# moire_v1_8.net
KiCad netlist of a schematic drawn in EAGLE
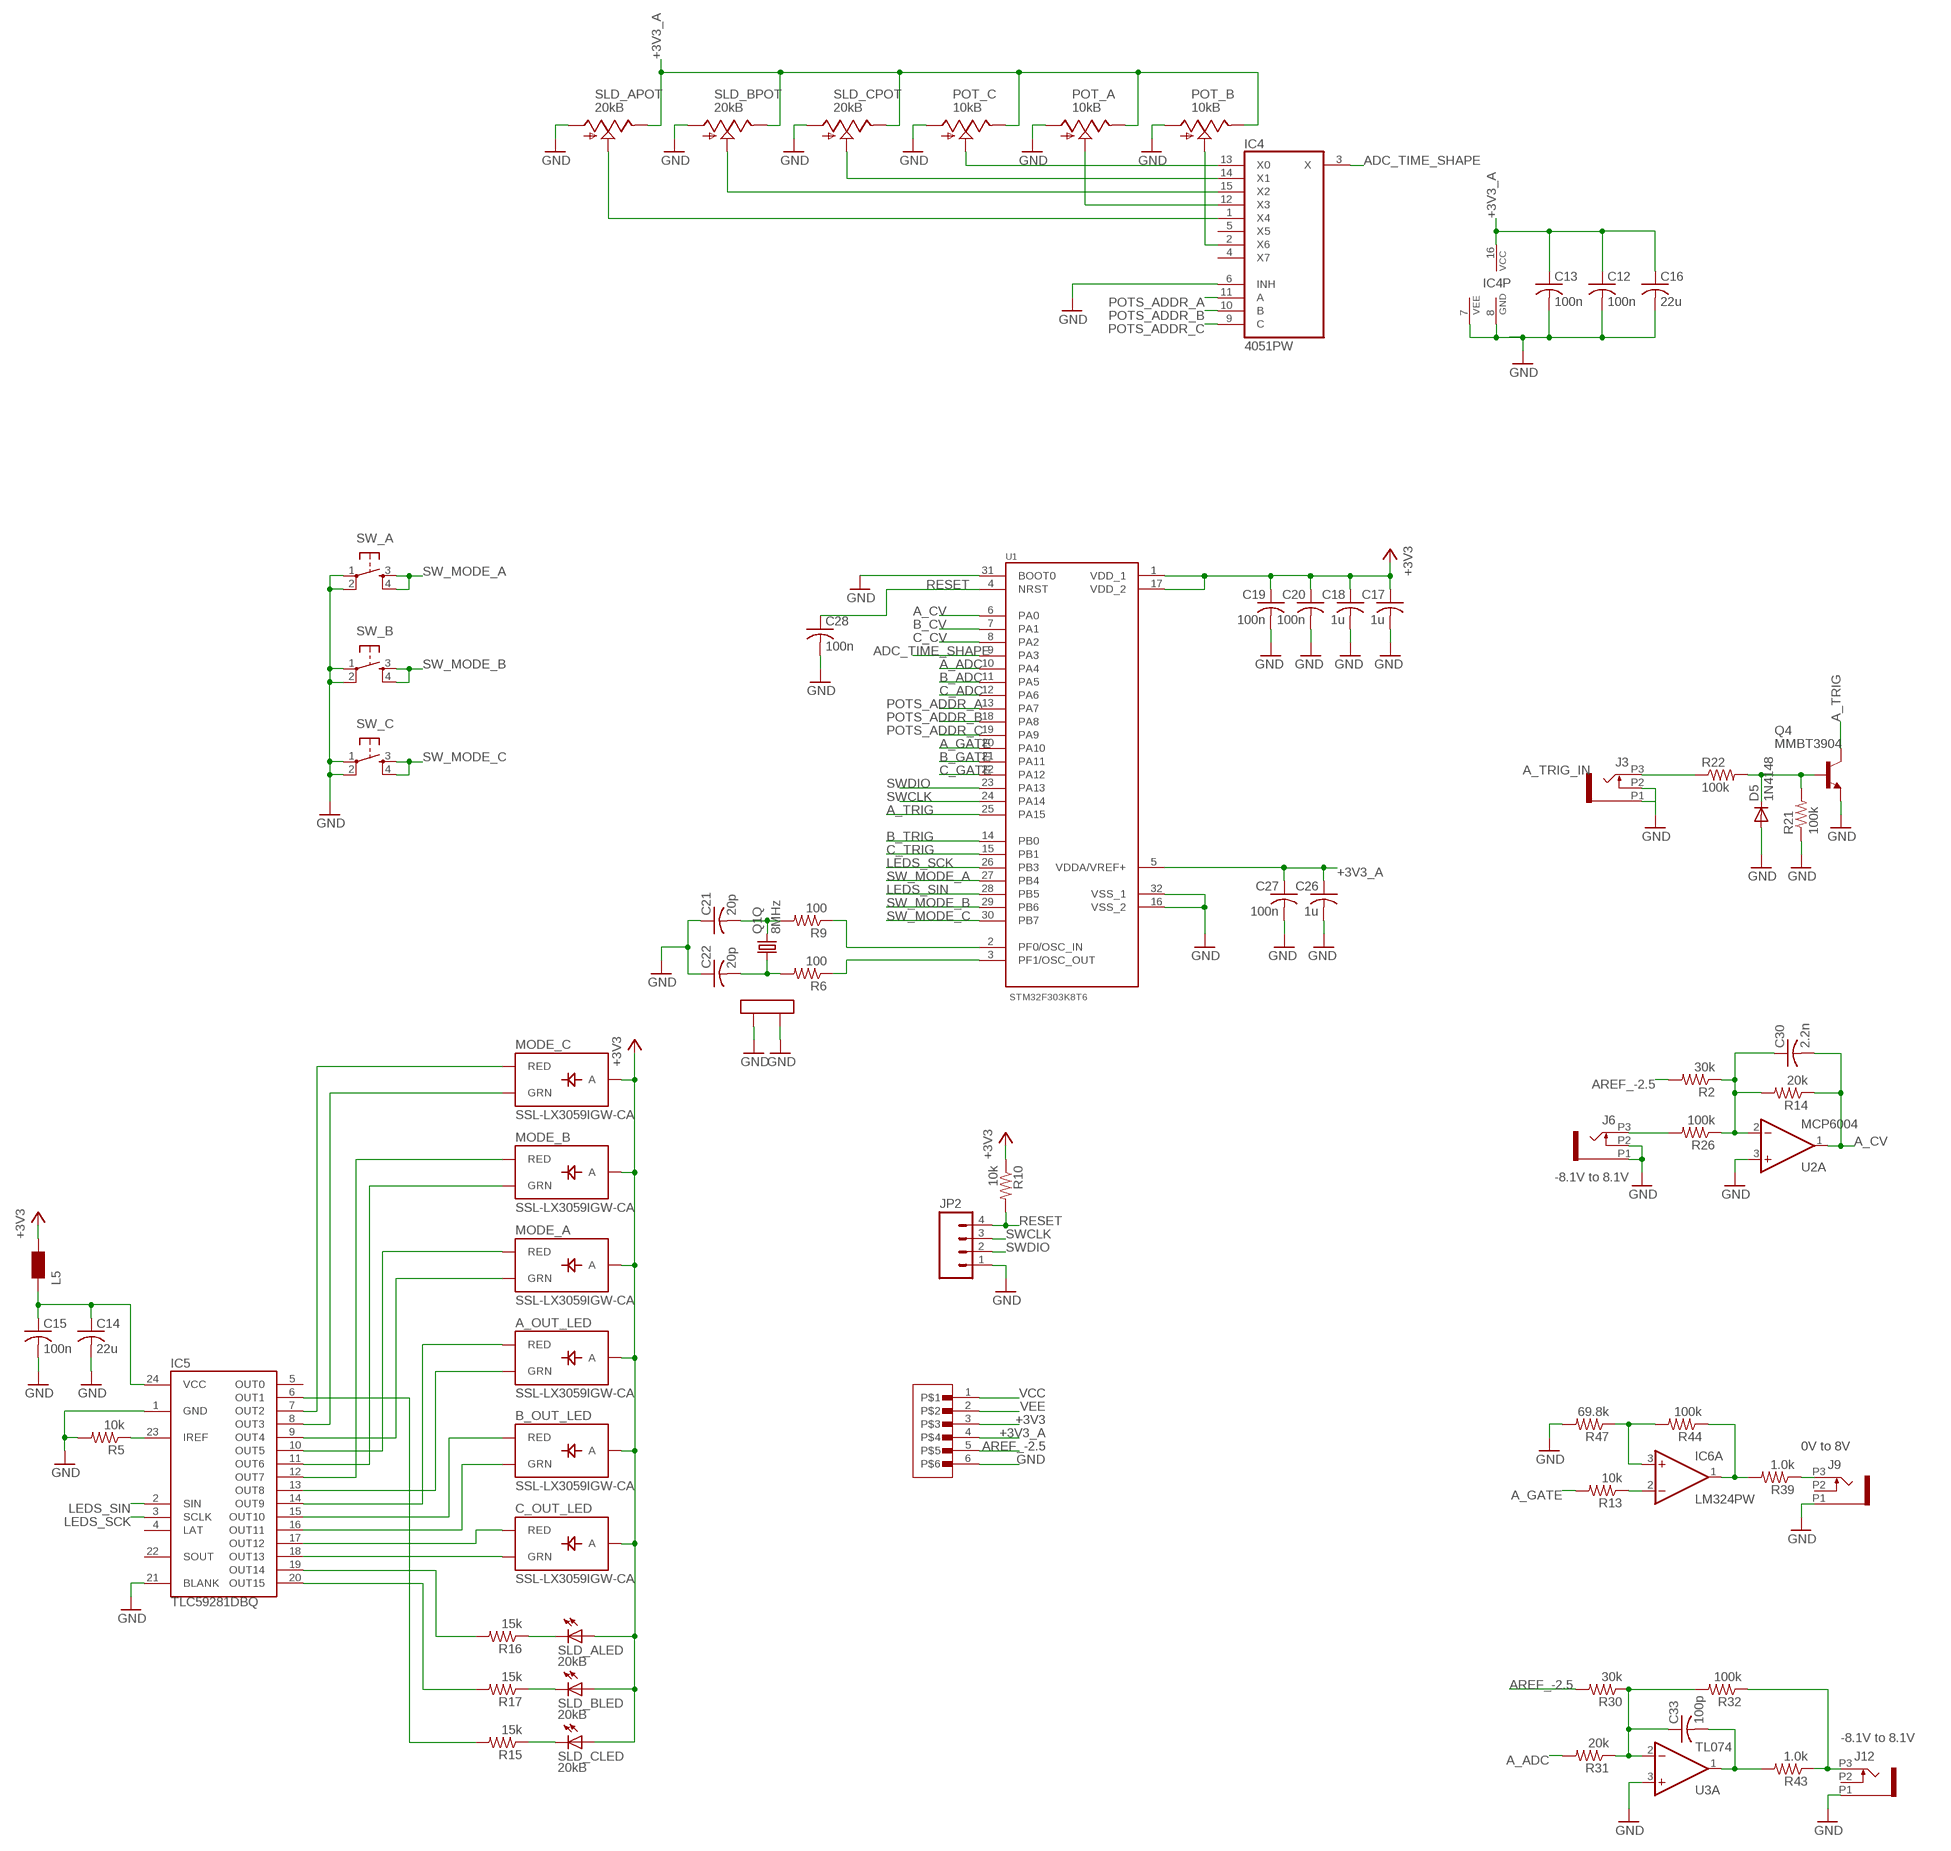
[diagram p0: schematic, sheet 1, part 1 of 2]
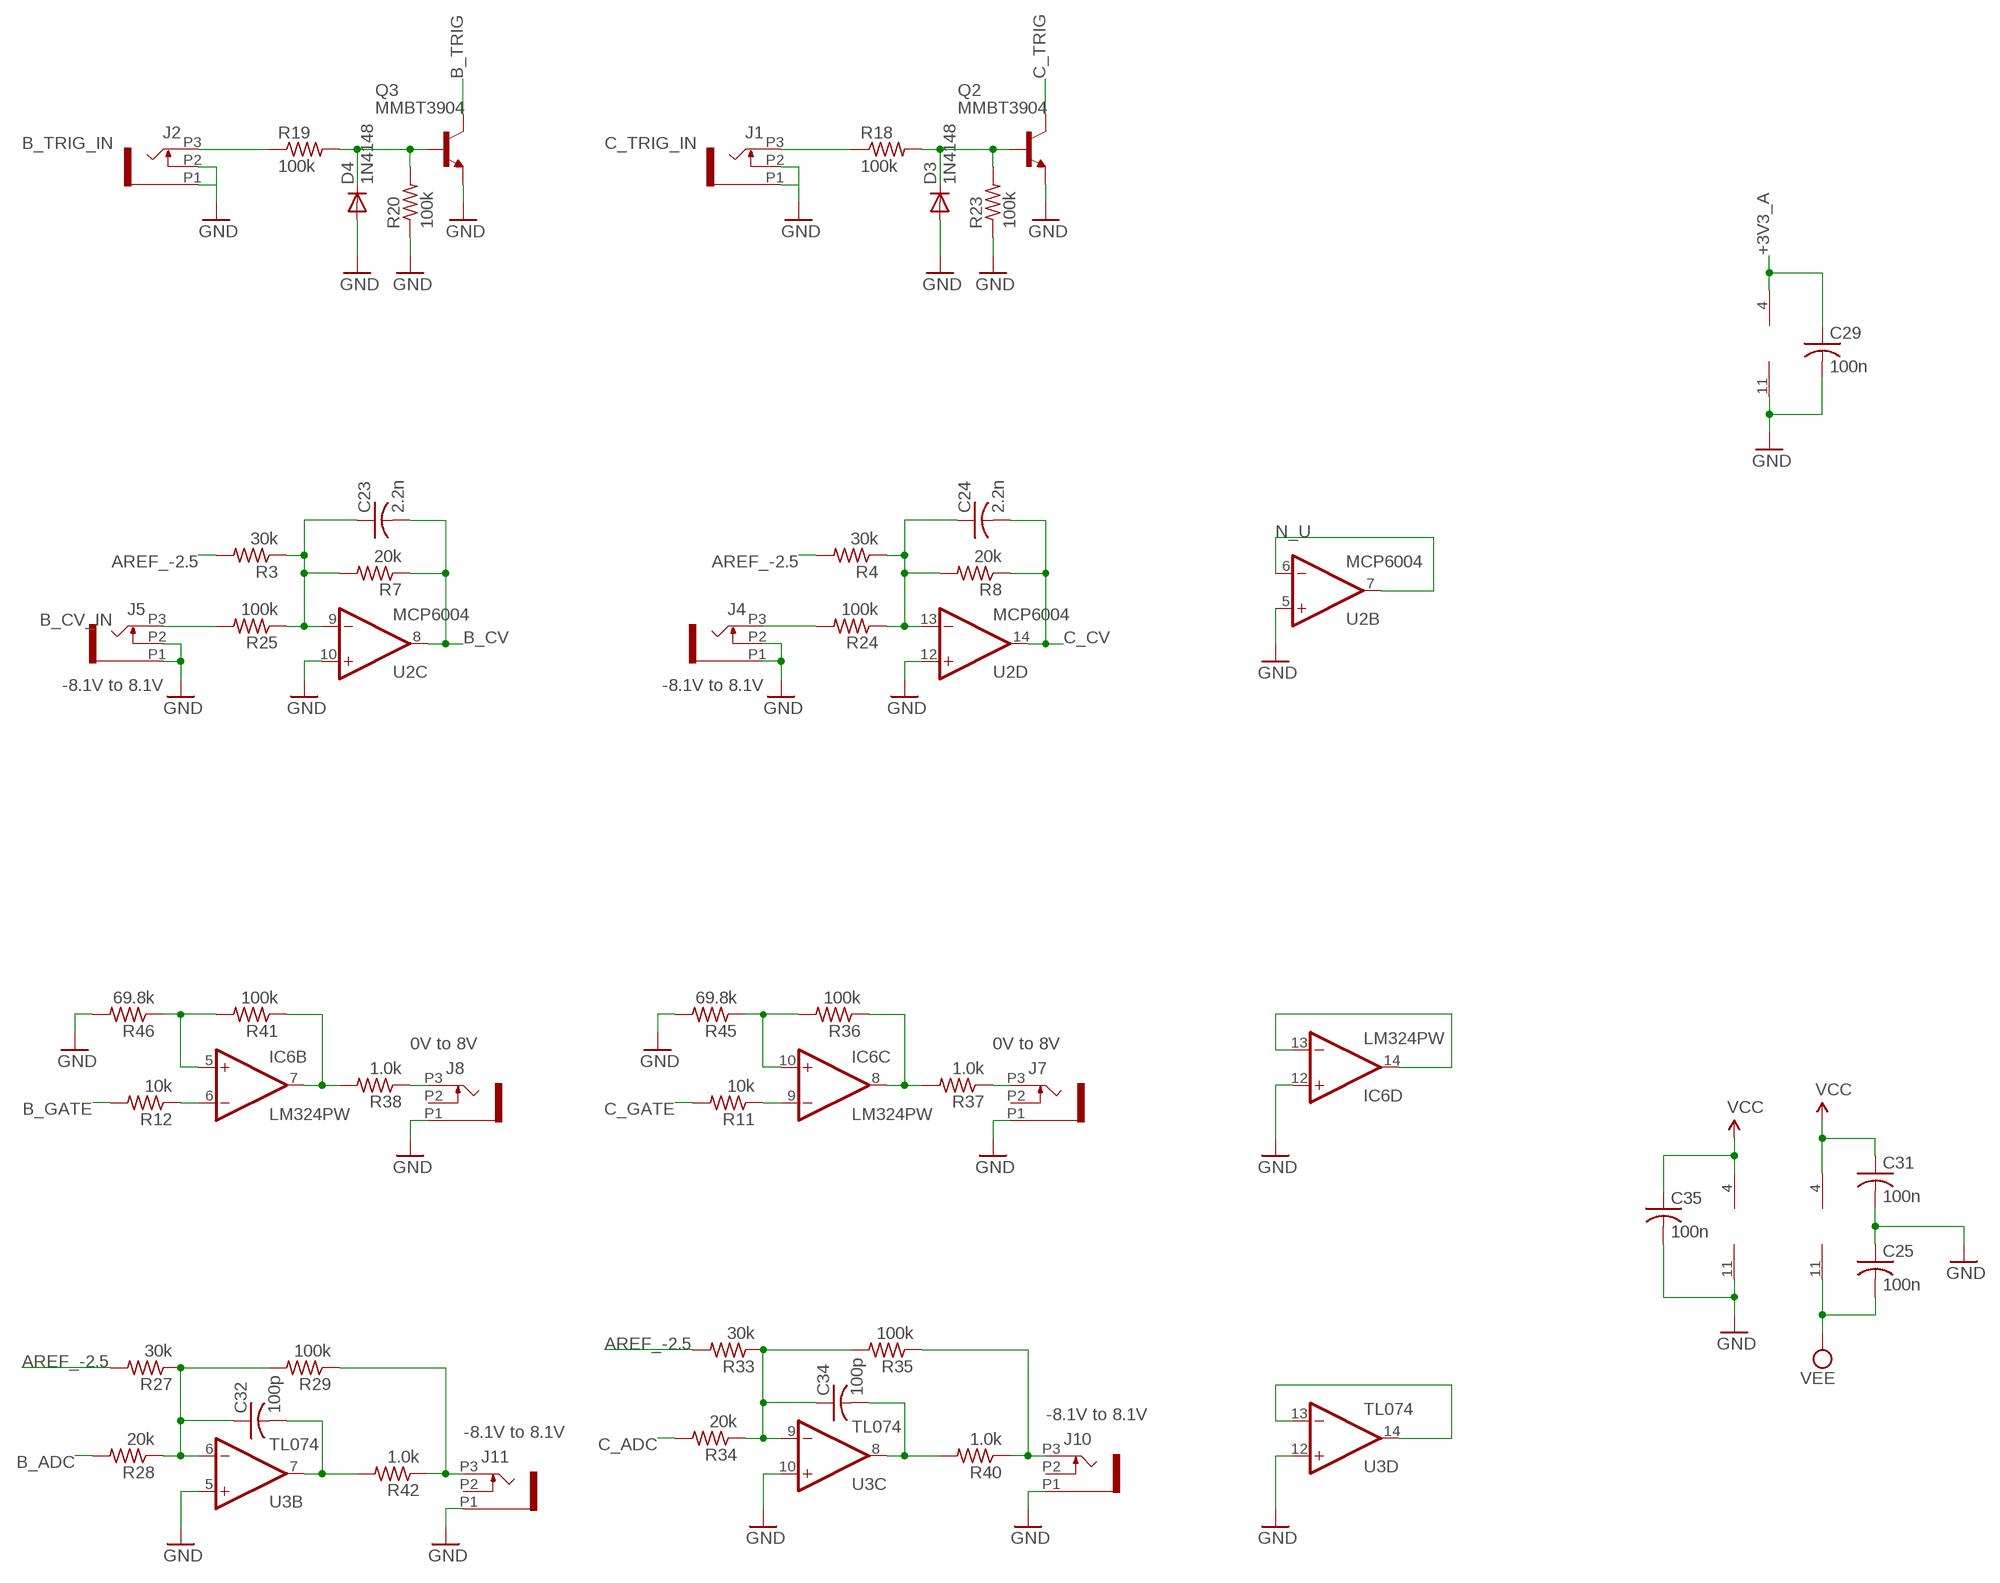
[diagram p1: schematic, sheet 1, part 2 of 2]
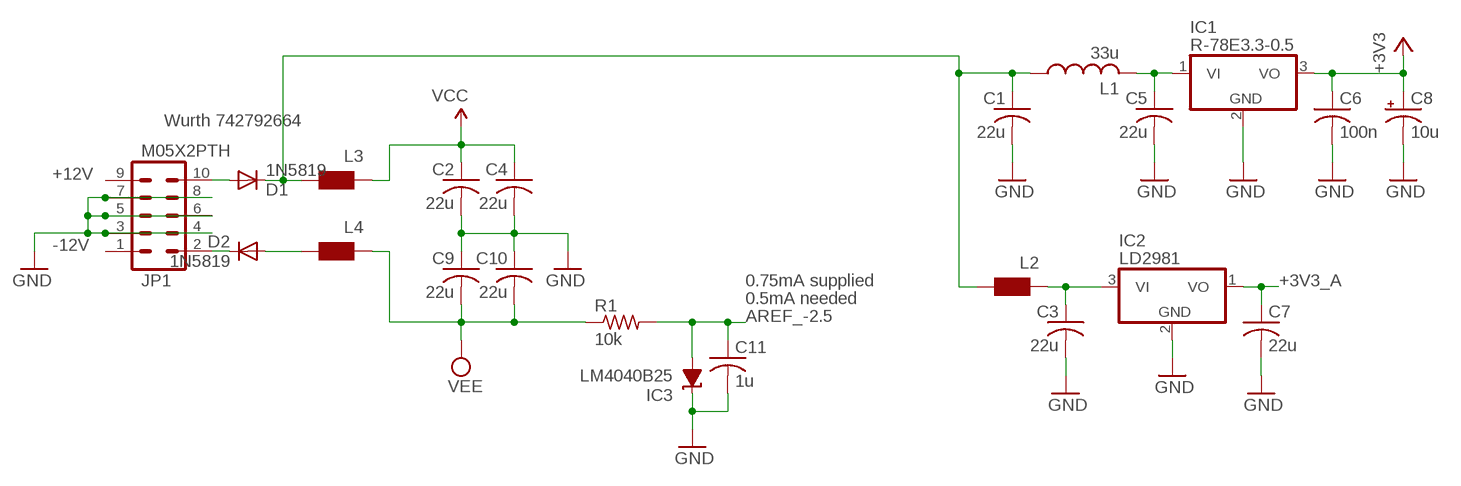
[diagram p2: schematic, sheet 2]

(export (version "E")
  (design (tool "Eeschema 10.0.6"))
  (components
    (comp (ref "C1")
      (value "22u")
      (footprint "eagle-import:RCL_C1206")
      (libsource (lib "eagle-import") (part "RCL_C-USC1206"))
    )
    (comp (ref "C2")
      (value "22u")
      (footprint "eagle-import:RCL_C1206")
      (libsource (lib "eagle-import") (part "RCL_C-USC1206"))
    )
    (comp (ref "C3")
      (value "22u")
      (footprint "eagle-import:RCL_C1206")
      (libsource (lib "eagle-import") (part "RCL_C-USC1206"))
    )
    (comp (ref "C4")
      (value "22u")
      (footprint "eagle-import:RCL_C1206")
      (libsource (lib "eagle-import") (part "RCL_C-USC1206"))
    )
    (comp (ref "C5")
      (value "22u")
      (footprint "eagle-import:RCL_C1206")
      (libsource (lib "eagle-import") (part "RCL_C-USC1206"))
    )
    (comp (ref "C6")
      (value "100n")
      (footprint "eagle-import:RCL_C0603")
      (libsource (lib "eagle-import") (part "RCL_C-USC0603"))
    )
    (comp (ref "C7")
      (value "22u")
      (footprint "eagle-import:RCL_C1206")
      (libsource (lib "eagle-import") (part "RCL_C-USC1206"))
    )
    (comp (ref "C8")
      (value "10u")
      (footprint "eagle-import:RCL_PANASONIC_A")
      (libsource (lib "eagle-import") (part "RCL_CPOL-USA"))
    )
    (comp (ref "C9")
      (value "22u")
      (footprint "eagle-import:RCL_C1206")
      (libsource (lib "eagle-import") (part "RCL_C-USC1206"))
    )
    (comp (ref "C10")
      (value "22u")
      (footprint "eagle-import:RCL_C1206")
      (libsource (lib "eagle-import") (part "RCL_C-USC1206"))
    )
    (comp (ref "C11")
      (value "1u")
      (footprint "eagle-import:RCL_C0603")
      (libsource (lib "eagle-import") (part "RCL_C-USC0603"))
    )
    (comp (ref "D1")
      (value "1N5819")
      (footprint "eagle-import:DIODE_SOD123")
      (libsource (lib "eagle-import") (part "DIODE_DIODE-SOD123"))
    )
    (comp (ref "D2")
      (value "1N5819")
      (footprint "eagle-import:DIODE_SOD123")
      (libsource (lib "eagle-import") (part "DIODE_DIODE-SOD123"))
    )
    (comp (ref "IC1")
      (value "R-78E3.3-0.5")
      (footprint "eagle-import:WE78")
      (libsource (lib "eagle-import") (part "WE173950378"))
    )
    (comp (ref "IC2")
      (value "LD2981")
      (footprint "eagle-import:SOT89")
      (libsource (lib "eagle-import") (part "LD2981ABU"))
    )
    (comp (ref "IC3")
      (value "LM4040B25")
      (footprint "eagle-import:DBZ_R-PDSO-G3")
      (libsource (lib "eagle-import") (part "LM4041DBZB12"))
    )
    (comp (ref "JP1")
      (value "M05X2PTH")
      (footprint "eagle-import:2X5-PTH")
      (libsource (lib "eagle-import") (part "M05X2PTH"))
    )
    (comp (ref "L1")
      (value "33u")
      (footprint "eagle-import:L2012C")
      (libsource (lib "eagle-import") (part "L-USL2012C"))
    )
    (comp (ref "L2")
      (value "WE-CBF_0603")
      (footprint "eagle-import:0603")
      (libsource (lib "eagle-import") (part "WE-CBF_0603"))
    )
    (comp (ref "L3")
      (value "WE-CBF_0603")
      (footprint "eagle-import:0603")
      (libsource (lib "eagle-import") (part "WE-CBF_0603"))
    )
    (comp (ref "L4")
      (value "WE-CBF_0603")
      (footprint "eagle-import:0603")
      (libsource (lib "eagle-import") (part "WE-CBF_0603"))
    )
    (comp (ref "R1")
      (value "10k")
      (footprint "eagle-import:RCL_R0603")
      (libsource (lib "eagle-import") (part "RCL_R-US_R0603"))
    )
    (comp (ref "A_OUT_LED")
      (value "SSL-LX3059IGW-CA")
      (footprint "eagle-import:LED-BICOLOR-THROUGHHOLE-LUMEX")
      (libsource (lib "eagle-import") (part "LED-BICOLOR-THROUGHHOLE-CA"))
    )
    (comp (ref "B_OUT_LED")
      (value "SSL-LX3059IGW-CA")
      (footprint "eagle-import:LED-BICOLOR-THROUGHHOLE-LUMEX")
      (libsource (lib "eagle-import") (part "LED-BICOLOR-THROUGHHOLE-CA"))
    )
    (comp (ref "C12")
      (value "100n")
      (footprint "eagle-import:RCL_C0603")
      (libsource (lib "eagle-import") (part "RCL_C-USC0603"))
    )
    (comp (ref "C13")
      (value "100n")
      (footprint "eagle-import:RCL_C0603")
      (libsource (lib "eagle-import") (part "RCL_C-USC0603"))
    )
    (comp (ref "C14")
      (value "22u")
      (footprint "eagle-import:RCL_C1206")
      (libsource (lib "eagle-import") (part "RCL_C-USC1206"))
    )
    (comp (ref "C15")
      (value "100n")
      (footprint "eagle-import:RCL_C0603")
      (libsource (lib "eagle-import") (part "RCL_C-USC0603"))
    )
    (comp (ref "C16")
      (value "22u")
      (footprint "eagle-import:RCL_C1206")
      (libsource (lib "eagle-import") (part "RCL_C-USC1206"))
    )
    (comp (ref "C17")
      (value "1u")
      (footprint "eagle-import:RCL_C0603")
      (libsource (lib "eagle-import") (part "RCL_C-USC0603"))
    )
    (comp (ref "C18")
      (value "1u")
      (footprint "eagle-import:RCL_C0603")
      (libsource (lib "eagle-import") (part "RCL_C-USC0603"))
    )
    (comp (ref "C19")
      (value "100n")
      (footprint "eagle-import:RCL_C0603")
      (libsource (lib "eagle-import") (part "RCL_C-USC0603"))
    )
    (comp (ref "C20")
      (value "100n")
      (footprint "eagle-import:RCL_C0603")
      (libsource (lib "eagle-import") (part "RCL_C-USC0603"))
    )
    (comp (ref "C21")
      (value "20p")
      (footprint "eagle-import:RCL_C0603")
      (libsource (lib "eagle-import") (part "RCL_C-USC0603"))
    )
    (comp (ref "C22")
      (value "20p")
      (footprint "eagle-import:RCL_C0603")
      (libsource (lib "eagle-import") (part "RCL_C-USC0603"))
    )
    (comp (ref "C23")
      (value "2.2n")
      (footprint "eagle-import:RCL_C0603")
      (libsource (lib "eagle-import") (part "RCL_C-USC0603"))
    )
    (comp (ref "C24")
      (value "2.2n")
      (footprint "eagle-import:RCL_C0603")
      (libsource (lib "eagle-import") (part "RCL_C-USC0603"))
    )
    (comp (ref "C25")
      (value "100n")
      (footprint "eagle-import:RCL_C0603")
      (libsource (lib "eagle-import") (part "RCL_C-USC0603"))
    )
    (comp (ref "C26")
      (value "1u")
      (footprint "eagle-import:RCL_C0603")
      (libsource (lib "eagle-import") (part "RCL_C-USC0603"))
    )
    (comp (ref "C27")
      (value "100n")
      (footprint "eagle-import:RCL_C0603")
      (libsource (lib "eagle-import") (part "RCL_C-USC0603"))
    )
    (comp (ref "C28")
      (value "100n")
      (footprint "eagle-import:RCL_C0603")
      (libsource (lib "eagle-import") (part "RCL_C-USC0603"))
    )
    (comp (ref "C29")
      (value "100n")
      (footprint "eagle-import:RCL_C0603")
      (libsource (lib "eagle-import") (part "RCL_C-USC0603"))
    )
    (comp (ref "C30")
      (value "2.2n")
      (footprint "eagle-import:RCL_C0603")
      (libsource (lib "eagle-import") (part "RCL_C-USC0603"))
    )
    (comp (ref "C31")
      (value "100n")
      (footprint "eagle-import:RCL_C0603")
      (libsource (lib "eagle-import") (part "RCL_C-USC0603"))
    )
    (comp (ref "C32")
      (value "100p")
      (footprint "eagle-import:RCL_C0603")
      (libsource (lib "eagle-import") (part "RCL_C-USC0603"))
    )
    (comp (ref "C33")
      (value "100p")
      (footprint "eagle-import:RCL_C0603")
      (libsource (lib "eagle-import") (part "RCL_C-USC0603"))
    )
    (comp (ref "C34")
      (value "100p")
      (footprint "eagle-import:RCL_C0603")
      (libsource (lib "eagle-import") (part "RCL_C-USC0603"))
    )
    (comp (ref "C35")
      (value "100n")
      (footprint "eagle-import:RCL_C0603")
      (libsource (lib "eagle-import") (part "RCL_C-USC0603"))
    )
    (comp (ref "C_OUT_LED")
      (value "SSL-LX3059IGW-CA")
      (footprint "eagle-import:LED-BICOLOR-THROUGHHOLE-LUMEX")
      (libsource (lib "eagle-import") (part "LED-BICOLOR-THROUGHHOLE-CA"))
    )
    (comp (ref "D3")
      (value "1N4148")
      (footprint "eagle-import:DIODE_SOD523")
      (libsource (lib "eagle-import") (part "DIODE_DIODE-SOD523"))
    )
    (comp (ref "D4")
      (value "1N4148")
      (footprint "eagle-import:DIODE_SOD523")
      (libsource (lib "eagle-import") (part "DIODE_DIODE-SOD523"))
    )
    (comp (ref "D5")
      (value "1N4148")
      (footprint "eagle-import:DIODE_SOD523")
      (libsource (lib "eagle-import") (part "DIODE_DIODE-SOD523"))
    )
    (comp (ref "IC4")
      (value "4051PW")
      (footprint "eagle-import:TSSOP16_065")
      (libsource (lib "eagle-import") (part "4051PW"))
    )
    (comp (ref "IC5")
      (value "TLC59281DBQ")
      (footprint "eagle-import:TSSOP24_0635")
      (libsource (lib "eagle-import") (part "TLC59281DBQ"))
    )
    (comp (ref "IC6")
      (value "LM324PW")
      (footprint "eagle-import:TSSOP14_065")
      (libsource (lib "eagle-import") (part "TL074PW"))
    )
    (comp (ref "J1")
      (value "PJ301_THONKICONN6")
      (footprint "eagle-import:WQP_PJ_301M6")
      (libsource (lib "eagle-import") (part "PJ301_THONKICONN6"))
    )
    (comp (ref "J2")
      (value "PJ301_THONKICONN6")
      (footprint "eagle-import:WQP_PJ_301M6")
      (libsource (lib "eagle-import") (part "PJ301_THONKICONN6"))
    )
    (comp (ref "J3")
      (value "PJ301_THONKICONN6")
      (footprint "eagle-import:WQP_PJ_301M6")
      (libsource (lib "eagle-import") (part "PJ301_THONKICONN6"))
    )
    (comp (ref "J4")
      (value "PJ301_THONKICONN6")
      (footprint "eagle-import:WQP_PJ_301M6")
      (libsource (lib "eagle-import") (part "PJ301_THONKICONN6"))
    )
    (comp (ref "J5")
      (value "PJ301_THONKICONN6")
      (footprint "eagle-import:WQP_PJ_301M6")
      (libsource (lib "eagle-import") (part "PJ301_THONKICONN6"))
    )
    (comp (ref "J6")
      (value "PJ301_THONKICONN6")
      (footprint "eagle-import:WQP_PJ_301M6")
      (libsource (lib "eagle-import") (part "PJ301_THONKICONN6"))
    )
    (comp (ref "J7")
      (value "PJ301_THONKICONN6")
      (footprint "eagle-import:WQP_PJ_301M6")
      (libsource (lib "eagle-import") (part "PJ301_THONKICONN6"))
    )
    (comp (ref "J8")
      (value "PJ301_THONKICONN6")
      (footprint "eagle-import:WQP_PJ_301M6")
      (libsource (lib "eagle-import") (part "PJ301_THONKICONN6"))
    )
    (comp (ref "J9")
      (value "PJ301_THONKICONN6")
      (footprint "eagle-import:WQP_PJ_301M6")
      (libsource (lib "eagle-import") (part "PJ301_THONKICONN6"))
    )
    (comp (ref "J10")
      (value "PJ301_THONKICONN6")
      (footprint "eagle-import:WQP_PJ_301M6")
      (libsource (lib "eagle-import") (part "PJ301_THONKICONN6"))
    )
    (comp (ref "J11")
      (value "PJ301_THONKICONN6")
      (footprint "eagle-import:WQP_PJ_301M6")
      (libsource (lib "eagle-import") (part "PJ301_THONKICONN6"))
    )
    (comp (ref "J12")
      (value "PJ301_THONKICONN6")
      (footprint "eagle-import:WQP_PJ_301M6")
      (libsource (lib "eagle-import") (part "PJ301_THONKICONN6"))
    )
    (comp (ref "JP2")
      (value "M04PTH")
      (footprint "eagle-import:1X04")
      (libsource (lib "eagle-import") (part "M04PTH"))
    )
    (comp (ref "L5")
      (value "WE-CBF_0603")
      (footprint "eagle-import:0603")
      (libsource (lib "eagle-import") (part "WE-CBF_0603"))
    )
    (comp (ref "MODE_A")
      (value "SSL-LX3059IGW-CA")
      (footprint "eagle-import:LED-BICOLOR-THROUGHHOLE-LUMEX")
      (libsource (lib "eagle-import") (part "LED-BICOLOR-THROUGHHOLE-CA"))
    )
    (comp (ref "MODE_B")
      (value "SSL-LX3059IGW-CA")
      (footprint "eagle-import:LED-BICOLOR-THROUGHHOLE-LUMEX")
      (libsource (lib "eagle-import") (part "LED-BICOLOR-THROUGHHOLE-CA"))
    )
    (comp (ref "MODE_C")
      (value "SSL-LX3059IGW-CA")
      (footprint "eagle-import:LED-BICOLOR-THROUGHHOLE-LUMEX")
      (libsource (lib "eagle-import") (part "LED-BICOLOR-THROUGHHOLE-CA"))
    )
    (comp (ref "POT_A")
      (value "10kB")
      (footprint "eagle-import:ALPS_POT_VERTICAL")
      (libsource (lib "eagle-import") (part "POT_USVERTICAL"))
    )
    (comp (ref "POT_B")
      (value "10kB")
      (footprint "eagle-import:ALPS_POT_VERTICAL")
      (libsource (lib "eagle-import") (part "POT_USVERTICAL"))
    )
    (comp (ref "POT_C")
      (value "10kB")
      (footprint "eagle-import:ALPS_POT_VERTICAL")
      (libsource (lib "eagle-import") (part "POT_USVERTICAL"))
    )
    (comp (ref "Q1")
      (value "8MHz")
      (footprint "eagle-import:CTS406")
      (libsource (lib "eagle-import") (part "CRYSTAL"))
    )
    (comp (ref "Q2")
      (value "MMBT3904")
      (footprint "eagle-import:SOT23-BEC")
      (libsource (lib "eagle-import") (part "-NPN-SOT23-BECMMBT3904LT1"))
    )
    (comp (ref "Q3")
      (value "MMBT3904")
      (footprint "eagle-import:SOT23-BEC")
      (libsource (lib "eagle-import") (part "-NPN-SOT23-BECMMBT3904LT1"))
    )
    (comp (ref "Q4")
      (value "MMBT3904")
      (footprint "eagle-import:SOT23-BEC")
      (libsource (lib "eagle-import") (part "-NPN-SOT23-BECMMBT3904LT1"))
    )
    (comp (ref "R2")
      (value "30k")
      (footprint "eagle-import:RCL_R0603")
      (libsource (lib "eagle-import") (part "RCL_R-US_R0603"))
    )
    (comp (ref "R3")
      (value "30k")
      (footprint "eagle-import:RCL_R0603")
      (libsource (lib "eagle-import") (part "RCL_R-US_R0603"))
    )
    (comp (ref "R4")
      (value "30k")
      (footprint "eagle-import:RCL_R0603")
      (libsource (lib "eagle-import") (part "RCL_R-US_R0603"))
    )
    (comp (ref "R5")
      (value "10k")
      (footprint "eagle-import:RCL_R0603")
      (libsource (lib "eagle-import") (part "RCL_R-US_R0603"))
    )
    (comp (ref "R6")
      (value "100")
      (footprint "eagle-import:RCL_R0603")
      (libsource (lib "eagle-import") (part "RCL_R-US_R0603"))
    )
    (comp (ref "R7")
      (value "20k")
      (footprint "eagle-import:RCL_R0603")
      (libsource (lib "eagle-import") (part "RCL_R-US_R0603"))
    )
    (comp (ref "R8")
      (value "20k")
      (footprint "eagle-import:RCL_R0603")
      (libsource (lib "eagle-import") (part "RCL_R-US_R0603"))
    )
    (comp (ref "R9")
      (value "100")
      (footprint "eagle-import:RCL_R0603")
      (libsource (lib "eagle-import") (part "RCL_R-US_R0603"))
    )
    (comp (ref "R10")
      (value "10k")
      (footprint "eagle-import:RCL_R0603")
      (libsource (lib "eagle-import") (part "RCL_R-US_R0603"))
    )
    (comp (ref "R11")
      (value "10k")
      (footprint "eagle-import:RCL_R0603")
      (libsource (lib "eagle-import") (part "RCL_R-US_R0603"))
    )
    (comp (ref "R12")
      (value "10k")
      (footprint "eagle-import:RCL_R0603")
      (libsource (lib "eagle-import") (part "RCL_R-US_R0603"))
    )
    (comp (ref "R13")
      (value "10k")
      (footprint "eagle-import:RCL_R0603")
      (libsource (lib "eagle-import") (part "RCL_R-US_R0603"))
    )
    (comp (ref "R14")
      (value "20k")
      (footprint "eagle-import:RCL_R0603")
      (libsource (lib "eagle-import") (part "RCL_R-US_R0603"))
    )
    (comp (ref "R15")
      (value "15k")
      (footprint "eagle-import:RCL_R0603")
      (libsource (lib "eagle-import") (part "RCL_R-US_R0603"))
    )
    (comp (ref "R16")
      (value "15k")
      (footprint "eagle-import:RCL_R0603")
      (libsource (lib "eagle-import") (part "RCL_R-US_R0603"))
    )
    (comp (ref "R17")
      (value "15k")
      (footprint "eagle-import:RCL_R0603")
      (libsource (lib "eagle-import") (part "RCL_R-US_R0603"))
    )
    (comp (ref "R18")
      (value "100k")
      (footprint "eagle-import:RCL_R0603")
      (libsource (lib "eagle-import") (part "RCL_R-US_R0603"))
    )
    (comp (ref "R19")
      (value "100k")
      (footprint "eagle-import:RCL_R0603")
      (libsource (lib "eagle-import") (part "RCL_R-US_R0603"))
    )
    (comp (ref "R20")
      (value "100k")
      (footprint "eagle-import:RCL_R0603")
      (libsource (lib "eagle-import") (part "RCL_R-US_R0603"))
    )
    (comp (ref "R21")
      (value "100k")
      (footprint "eagle-import:RCL_R0603")
      (libsource (lib "eagle-import") (part "RCL_R-US_R0603"))
    )
    (comp (ref "R22")
      (value "100k")
      (footprint "eagle-import:RCL_R0603")
      (libsource (lib "eagle-import") (part "RCL_R-US_R0603"))
    )
    (comp (ref "R23")
      (value "100k")
      (footprint "eagle-import:RCL_R0603")
      (libsource (lib "eagle-import") (part "RCL_R-US_R0603"))
    )
    (comp (ref "R24")
      (value "100k")
      (footprint "eagle-import:RCL_R0603")
      (libsource (lib "eagle-import") (part "RCL_R-US_R0603"))
    )
    (comp (ref "R25")
      (value "100k")
      (footprint "eagle-import:RCL_R0603")
      (libsource (lib "eagle-import") (part "RCL_R-US_R0603"))
    )
    (comp (ref "R26")
      (value "100k")
      (footprint "eagle-import:RCL_R0603")
      (libsource (lib "eagle-import") (part "RCL_R-US_R0603"))
    )
    (comp (ref "R27")
      (value "30k")
      (footprint "eagle-import:RCL_R0603")
      (libsource (lib "eagle-import") (part "RCL_R-US_R0603"))
    )
    (comp (ref "R28")
      (value "20k")
      (footprint "eagle-import:RCL_R0603")
      (libsource (lib "eagle-import") (part "RCL_R-US_R0603"))
    )
    (comp (ref "R29")
      (value "100k")
      (footprint "eagle-import:RCL_R0603")
      (libsource (lib "eagle-import") (part "RCL_R-US_R0603"))
    )
    (comp (ref "R30")
      (value "30k")
      (footprint "eagle-import:RCL_R0603")
      (libsource (lib "eagle-import") (part "RCL_R-US_R0603"))
    )
    (comp (ref "R31")
      (value "20k")
      (footprint "eagle-import:RCL_R0603")
      (libsource (lib "eagle-import") (part "RCL_R-US_R0603"))
    )
    (comp (ref "R32")
      (value "100k")
      (footprint "eagle-import:RCL_R0603")
      (libsource (lib "eagle-import") (part "RCL_R-US_R0603"))
    )
    (comp (ref "R33")
      (value "30k")
      (footprint "eagle-import:RCL_R0603")
      (libsource (lib "eagle-import") (part "RCL_R-US_R0603"))
    )
    (comp (ref "R34")
      (value "20k")
      (footprint "eagle-import:RCL_R0603")
      (libsource (lib "eagle-import") (part "RCL_R-US_R0603"))
    )
    (comp (ref "R35")
      (value "100k")
      (footprint "eagle-import:RCL_R0603")
      (libsource (lib "eagle-import") (part "RCL_R-US_R0603"))
    )
    (comp (ref "R36")
      (value "100k")
      (footprint "eagle-import:RCL_R0603")
      (libsource (lib "eagle-import") (part "RCL_R-US_R0603"))
    )
    (comp (ref "R37")
      (value "1.0k")
      (footprint "eagle-import:RCL_R0603")
      (libsource (lib "eagle-import") (part "RCL_R-US_R0603"))
    )
    (comp (ref "R38")
      (value "1.0k")
      (footprint "eagle-import:RCL_R0603")
      (libsource (lib "eagle-import") (part "RCL_R-US_R0603"))
    )
    (comp (ref "R39")
      (value "1.0k")
      (footprint "eagle-import:RCL_R0603")
      (libsource (lib "eagle-import") (part "RCL_R-US_R0603"))
    )
    (comp (ref "R40")
      (value "1.0k")
      (footprint "eagle-import:RCL_R0603")
      (libsource (lib "eagle-import") (part "RCL_R-US_R0603"))
    )
    (comp (ref "R41")
      (value "100k")
      (footprint "eagle-import:RCL_R0603")
      (libsource (lib "eagle-import") (part "RCL_R-US_R0603"))
    )
    (comp (ref "R42")
      (value "1.0k")
      (footprint "eagle-import:RCL_R0603")
      (libsource (lib "eagle-import") (part "RCL_R-US_R0603"))
    )
    (comp (ref "R43")
      (value "1.0k")
      (footprint "eagle-import:RCL_R0603")
      (libsource (lib "eagle-import") (part "RCL_R-US_R0603"))
    )
    (comp (ref "R44")
      (value "100k")
      (footprint "eagle-import:RCL_R0603")
      (libsource (lib "eagle-import") (part "RCL_R-US_R0603"))
    )
    (comp (ref "R45")
      (value "69.8k")
      (footprint "eagle-import:RCL_R0603")
      (libsource (lib "eagle-import") (part "RCL_R-US_R0603"))
    )
    (comp (ref "R46")
      (value "69.8k")
      (footprint "eagle-import:RCL_R0603")
      (libsource (lib "eagle-import") (part "RCL_R-US_R0603"))
    )
    (comp (ref "R47")
      (value "69.8k")
      (footprint "eagle-import:RCL_R0603")
      (libsource (lib "eagle-import") (part "RCL_R-US_R0603"))
    )
    (comp (ref "SLD_A")
      (value "20kB")
      (footprint "eagle-import:BOURNS_SLIDER")
      (libsource (lib "eagle-import") (part "BOURNS_SLIDER"))
    )
    (comp (ref "SLD_B")
      (value "20kB")
      (footprint "eagle-import:BOURNS_SLIDER")
      (libsource (lib "eagle-import") (part "BOURNS_SLIDER"))
    )
    (comp (ref "SLD_C")
      (value "20kB")
      (footprint "eagle-import:BOURNS_SLIDER")
      (libsource (lib "eagle-import") (part "BOURNS_SLIDER"))
    )
    (comp (ref "SW_A")
      (value "TAC_SWITCHPTH")
      (footprint "eagle-import:TACTILE-PTH")
      (libsource (lib "eagle-import") (part "TAC_SWITCHPTH"))
    )
    (comp (ref "SW_B")
      (value "TAC_SWITCHPTH")
      (footprint "eagle-import:TACTILE-PTH")
      (libsource (lib "eagle-import") (part "TAC_SWITCHPTH"))
    )
    (comp (ref "SW_C")
      (value "TAC_SWITCHPTH")
      (footprint "eagle-import:TACTILE-PTH")
      (libsource (lib "eagle-import") (part "TAC_SWITCHPTH"))
    )
    (comp (ref "U$1")
      (value "1X6-SMD-TESTPAD")
      (footprint "eagle-import:6X1-SMD-TESTPAD")
      (libsource (lib "eagle-import") (part "1X6-SMD-TESTPAD"))
    )
    (comp (ref "U1")
      (value "STM32F303K8T6")
      (footprint "eagle-import:QFP80P900X900X160-32N")
      (fields (field (name "MF") "STMicroelectronics"))
      (libsource (lib "eagle-import") (part "STM32F303K8T6"))
    )
    (comp (ref "U2")
      (value "MCP6004")
      (footprint "eagle-import:SO14")
      (libsource (lib "eagle-import") (part "MCP6004_SMD"))
    )
    (comp (ref "U3")
      (value "TL074")
      (footprint "eagle-import:SO14")
      (libsource (lib "eagle-import") (part "TL074_SMD"))
    )
  )
  (nets
    (net (code "1") (name "+3V3") (class "Default")
      (node (ref "A_OUT_LED") (pin "A") (pinfunction "A_A") (pintype "bidirectional"))
      (node (ref "B_OUT_LED") (pin "A") (pinfunction "A_A") (pintype "bidirectional"))
      (node (ref "C17") (pin "1") (pinfunction "1_1") (pintype "passive"))
      (node (ref "C18") (pin "1") (pinfunction "1_1") (pintype "passive"))
      (node (ref "C19") (pin "1") (pinfunction "1_1") (pintype "passive"))
      (node (ref "C20") (pin "1") (pinfunction "1_1") (pintype "passive"))
      (node (ref "C6") (pin "1") (pinfunction "1_1") (pintype "passive"))
      (node (ref "C8") (pin "+") (pinfunction "+_+") (pintype "passive"))
      (node (ref "C_OUT_LED") (pin "A") (pinfunction "A_A") (pintype "bidirectional"))
      (node (ref "IC1") (pin "3") (pinfunction "VO_3") (pintype "passive"))
      (node (ref "L5") (pin "2") (pinfunction "2_2") (pintype "passive"))
      (node (ref "MODE_A") (pin "A") (pinfunction "A_A") (pintype "bidirectional"))
      (node (ref "MODE_B") (pin "A") (pinfunction "A_A") (pintype "bidirectional"))
      (node (ref "MODE_C") (pin "A") (pinfunction "A_A") (pintype "bidirectional"))
      (node (ref "R10") (pin "1") (pinfunction "1_1") (pintype "passive"))
      (node (ref "SLD_A") (pin "B") (pinfunction "A_B") (pintype "passive"))
      (node (ref "SLD_B") (pin "B") (pinfunction "A_B") (pintype "passive"))
      (node (ref "SLD_C") (pin "B") (pinfunction "A_B") (pintype "passive"))
      (node (ref "U$1") (pin "3") (pinfunction "P$3_3") (pintype "bidirectional"))
      (node (ref "U1") (pin "1") (pinfunction "VDD_1_1") (pintype "power_in"))
      (node (ref "U1") (pin "17") (pinfunction "VDD_2_17") (pintype "power_in"))
    )
    (net (code "2") (name "+3V3_A") (class "Default")
      (node (ref "C12") (pin "1") (pinfunction "1_1") (pintype "passive"))
      (node (ref "C13") (pin "1") (pinfunction "1_1") (pintype "passive"))
      (node (ref "C16") (pin "1") (pinfunction "1_1") (pintype "passive"))
      (node (ref "C26") (pin "1") (pinfunction "1_1") (pintype "passive"))
      (node (ref "C27") (pin "1") (pinfunction "1_1") (pintype "passive"))
      (node (ref "C29") (pin "1") (pinfunction "1_1") (pintype "passive"))
      (node (ref "C7") (pin "1") (pinfunction "1_1") (pintype "passive"))
      (node (ref "IC2") (pin "1") (pinfunction "VO_1") (pintype "passive"))
      (node (ref "IC4") (pin "16") (pinfunction "VCC_16") (pintype "power_in"))
      (node (ref "POT_A") (pin "P$1") (pinfunction "E_P$1") (pintype "passive"))
      (node (ref "POT_B") (pin "P$1") (pinfunction "E_P$1") (pintype "passive"))
      (node (ref "POT_C") (pin "P$1") (pinfunction "E_P$1") (pintype "passive"))
      (node (ref "SLD_A") (pin "3") (pinfunction "E_3") (pintype "passive"))
      (node (ref "SLD_B") (pin "3") (pinfunction "E_3") (pintype "passive"))
      (node (ref "SLD_C") (pin "3") (pinfunction "E_3") (pintype "passive"))
      (node (ref "U$1") (pin "4") (pinfunction "P$4_4") (pintype "bidirectional"))
      (node (ref "U1") (pin "5") (pinfunction "VDDA/VREF+_5") (pintype "power_in"))
      (node (ref "U2") (pin "4") (pinfunction "V+_4") (pintype "power_in"))
    )
    (net (code "3") (name "+12V") (class "Default")
      (node (ref "D1") (pin "A") (pinfunction "A_A") (pintype "passive"))
      (node (ref "JP1") (pin "10") (pinfunction "10_10") (pintype "passive"))
      (node (ref "JP1") (pin "9") (pinfunction "9_9") (pintype "passive"))
    )
    (net (code "4") (name "-12V") (class "Default")
      (node (ref "D2") (pin "C") (pinfunction "C_C") (pintype "passive"))
      (node (ref "JP1") (pin "1") (pinfunction "1_1") (pintype "passive"))
      (node (ref "JP1") (pin "2") (pinfunction "2_2") (pintype "passive"))
    )
    (net (code "5") (name "ADC_TIME_SHAPE") (class "Default")
      (node (ref "IC4") (pin "3") (pinfunction "X_3") (pintype "bidirectional"))
      (node (ref "U1") (pin "9") (pinfunction "PA3_9") (pintype "bidirectional"))
    )
    (net (code "6") (name "AREF_-2.5") (class "Default")
      (node (ref "C11") (pin "1") (pinfunction "1_1") (pintype "passive"))
      (node (ref "IC3") (pin "2") (pinfunction "A_2") (pintype "passive"))
      (node (ref "R1") (pin "2") (pinfunction "2_2") (pintype "passive"))
      (node (ref "R2") (pin "2") (pinfunction "2_2") (pintype "passive"))
      (node (ref "R27") (pin "2") (pinfunction "2_2") (pintype "passive"))
      (node (ref "R3") (pin "2") (pinfunction "2_2") (pintype "passive"))
      (node (ref "R30") (pin "2") (pinfunction "2_2") (pintype "passive"))
      (node (ref "R33") (pin "2") (pinfunction "2_2") (pintype "passive"))
      (node (ref "R4") (pin "2") (pinfunction "2_2") (pintype "passive"))
      (node (ref "U$1") (pin "5") (pinfunction "P$5_5") (pintype "bidirectional"))
    )
    (net (code "7") (name "A_ADC") (class "Default")
      (node (ref "R31") (pin "2") (pinfunction "2_2") (pintype "passive"))
      (node (ref "U1") (pin "10") (pinfunction "PA4_10") (pintype "bidirectional"))
    )
    (net (code "8") (name "A_CV") (class "Default")
      (node (ref "C30") (pin "2") (pinfunction "2_2") (pintype "passive"))
      (node (ref "R14") (pin "1") (pinfunction "1_1") (pintype "passive"))
      (node (ref "U1") (pin "6") (pinfunction "PA0_6") (pintype "bidirectional"))
      (node (ref "U2") (pin "1") (pinfunction "OUT_1") (pintype "output"))
    )
    (net (code "9") (name "A_GATE") (class "Default")
      (node (ref "R13") (pin "2") (pinfunction "2_2") (pintype "passive"))
      (node (ref "U1") (pin "20") (pinfunction "PA10_20") (pintype "bidirectional"))
    )
    (net (code "10") (name "A_TRIG") (class "Default")
      (node (ref "Q4") (pin "C") (pinfunction "C_C") (pintype "passive"))
      (node (ref "U1") (pin "25") (pinfunction "PA15_25") (pintype "bidirectional"))
    )
    (net (code "11") (name "A_TRIG_IN") (class "Default")
      (node (ref "J3") (pin "P3") (pinfunction "3_P3") (pintype "passive"))
      (node (ref "R22") (pin "1") (pinfunction "1_1") (pintype "passive"))
    )
    (net (code "12") (name "B_ADC") (class "Default")
      (node (ref "R28") (pin "2") (pinfunction "2_2") (pintype "passive"))
      (node (ref "U1") (pin "11") (pinfunction "PA5_11") (pintype "bidirectional"))
    )
    (net (code "13") (name "B_CV") (class "Default")
      (node (ref "C23") (pin "2") (pinfunction "2_2") (pintype "passive"))
      (node (ref "R7") (pin "1") (pinfunction "1_1") (pintype "passive"))
      (node (ref "U1") (pin "7") (pinfunction "PA1_7") (pintype "bidirectional"))
      (node (ref "U2") (pin "8") (pinfunction "OUT_8") (pintype "output"))
    )
    (net (code "14") (name "B_CV_IN") (class "Default")
      (node (ref "J5") (pin "P3") (pinfunction "3_P3") (pintype "passive"))
      (node (ref "R25") (pin "2") (pinfunction "2_2") (pintype "passive"))
    )
    (net (code "15") (name "B_GATE") (class "Default")
      (node (ref "R12") (pin "2") (pinfunction "2_2") (pintype "passive"))
      (node (ref "U1") (pin "21") (pinfunction "PA11_21") (pintype "bidirectional"))
    )
    (net (code "16") (name "B_TRIG") (class "Default")
      (node (ref "Q3") (pin "C") (pinfunction "C_C") (pintype "passive"))
      (node (ref "U1") (pin "14") (pinfunction "PB0_14") (pintype "bidirectional"))
    )
    (net (code "17") (name "B_TRIG_IN") (class "Default")
      (node (ref "J2") (pin "P3") (pinfunction "3_P3") (pintype "passive"))
      (node (ref "R19") (pin "1") (pinfunction "1_1") (pintype "passive"))
    )
    (net (code "18") (name "C_ADC") (class "Default")
      (node (ref "R34") (pin "2") (pinfunction "2_2") (pintype "passive"))
      (node (ref "U1") (pin "12") (pinfunction "PA6_12") (pintype "bidirectional"))
    )
    (net (code "19") (name "C_CV") (class "Default")
      (node (ref "C24") (pin "2") (pinfunction "2_2") (pintype "passive"))
      (node (ref "R8") (pin "1") (pinfunction "1_1") (pintype "passive"))
      (node (ref "U1") (pin "8") (pinfunction "PA2_8") (pintype "bidirectional"))
      (node (ref "U2") (pin "14") (pinfunction "OUT_14") (pintype "output"))
    )
    (net (code "20") (name "C_GATE") (class "Default")
      (node (ref "R11") (pin "2") (pinfunction "2_2") (pintype "passive"))
      (node (ref "U1") (pin "22") (pinfunction "PA12_22") (pintype "bidirectional"))
    )
    (net (code "21") (name "C_TRIG") (class "Default")
      (node (ref "Q2") (pin "C") (pinfunction "C_C") (pintype "passive"))
      (node (ref "U1") (pin "15") (pinfunction "PB1_15") (pintype "bidirectional"))
    )
    (net (code "22") (name "C_TRIG_IN") (class "Default")
      (node (ref "J1") (pin "P3") (pinfunction "3_P3") (pintype "passive"))
      (node (ref "R18") (pin "1") (pinfunction "1_1") (pintype "passive"))
    )
    (net (code "23") (name "GND") (class "Default")
      (node (ref "C1") (pin "2") (pinfunction "2_2") (pintype "passive"))
      (node (ref "C10") (pin "1") (pinfunction "1_1") (pintype "passive"))
      (node (ref "C11") (pin "2") (pinfunction "2_2") (pintype "passive"))
      (node (ref "C12") (pin "2") (pinfunction "2_2") (pintype "passive"))
      (node (ref "C13") (pin "2") (pinfunction "2_2") (pintype "passive"))
      (node (ref "C14") (pin "2") (pinfunction "2_2") (pintype "passive"))
      (node (ref "C15") (pin "2") (pinfunction "2_2") (pintype "passive"))
      (node (ref "C16") (pin "2") (pinfunction "2_2") (pintype "passive"))
      (node (ref "C17") (pin "2") (pinfunction "2_2") (pintype "passive"))
      (node (ref "C18") (pin "2") (pinfunction "2_2") (pintype "passive"))
      (node (ref "C19") (pin "2") (pinfunction "2_2") (pintype "passive"))
      (node (ref "C2") (pin "2") (pinfunction "2_2") (pintype "passive"))
      (node (ref "C20") (pin "2") (pinfunction "2_2") (pintype "passive"))
      (node (ref "C21") (pin "1") (pinfunction "1_1") (pintype "passive"))
      (node (ref "C22") (pin "1") (pinfunction "1_1") (pintype "passive"))
      (node (ref "C25") (pin "1") (pinfunction "1_1") (pintype "passive"))
      (node (ref "C26") (pin "2") (pinfunction "2_2") (pintype "passive"))
      (node (ref "C27") (pin "2") (pinfunction "2_2") (pintype "passive"))
      (node (ref "C28") (pin "2") (pinfunction "2_2") (pintype "passive"))
      (node (ref "C29") (pin "2") (pinfunction "2_2") (pintype "passive"))
      (node (ref "C3") (pin "2") (pinfunction "2_2") (pintype "passive"))
      (node (ref "C31") (pin "2") (pinfunction "2_2") (pintype "passive"))
      (node (ref "C35") (pin "2") (pinfunction "2_2") (pintype "passive"))
      (node (ref "C4") (pin "2") (pinfunction "2_2") (pintype "passive"))
      (node (ref "C5") (pin "2") (pinfunction "2_2") (pintype "passive"))
      (node (ref "C6") (pin "2") (pinfunction "2_2") (pintype "passive"))
      (node (ref "C7") (pin "2") (pinfunction "2_2") (pintype "passive"))
      (node (ref "C8") (pin "-") (pinfunction "-_-") (pintype "passive"))
      (node (ref "C9") (pin "1") (pinfunction "1_1") (pintype "passive"))
      (node (ref "D3") (pin "A") (pinfunction "A_A") (pintype "passive"))
      (node (ref "D4") (pin "A") (pinfunction "A_A") (pintype "passive"))
      (node (ref "D5") (pin "A") (pinfunction "A_A") (pintype "passive"))
      (node (ref "IC1") (pin "2") (pinfunction "GND_2") (pintype "passive"))
      (node (ref "IC2") (pin "2") (pinfunction "GND_2") (pintype "passive"))
      (node (ref "IC3") (pin "1") (pinfunction "C_1") (pintype "passive"))
      (node (ref "IC4") (pin "6") (pinfunction "INH_6") (pintype "input"))
      (node (ref "IC4") (pin "7") (pinfunction "VEE_7") (pintype "power_in"))
      (node (ref "IC4") (pin "8") (pinfunction "GND_8") (pintype "power_in"))
      (node (ref "IC5") (pin "1") (pinfunction "GND_1") (pintype "bidirectional"))
      (node (ref "IC5") (pin "21") (pinfunction "BLANK_21") (pintype "bidirectional"))
      (node (ref "IC6") (pin "11") (pinfunction "V-_11") (pintype "power_in"))
      (node (ref "IC6") (pin "12") (pinfunction "+IN_12") (pintype "input"))
      (node (ref "J1") (pin "P1") (pinfunction "1_P1") (pintype "passive"))
      (node (ref "J1") (pin "P2") (pinfunction "2_P2") (pintype "passive"))
      (node (ref "J10") (pin "P1") (pinfunction "1_P1") (pintype "passive"))
      (node (ref "J11") (pin "P1") (pinfunction "1_P1") (pintype "passive"))
      (node (ref "J12") (pin "P1") (pinfunction "1_P1") (pintype "passive"))
      (node (ref "J2") (pin "P1") (pinfunction "1_P1") (pintype "passive"))
      (node (ref "J2") (pin "P2") (pinfunction "2_P2") (pintype "passive"))
      (node (ref "J3") (pin "P1") (pinfunction "1_P1") (pintype "passive"))
      (node (ref "J3") (pin "P2") (pinfunction "2_P2") (pintype "passive"))
      (node (ref "J4") (pin "P1") (pinfunction "1_P1") (pintype "passive"))
      (node (ref "J4") (pin "P2") (pinfunction "2_P2") (pintype "passive"))
      (node (ref "J5") (pin "P1") (pinfunction "1_P1") (pintype "passive"))
      (node (ref "J5") (pin "P2") (pinfunction "2_P2") (pintype "passive"))
      (node (ref "J6") (pin "P1") (pinfunction "1_P1") (pintype "passive"))
      (node (ref "J6") (pin "P2") (pinfunction "2_P2") (pintype "passive"))
      (node (ref "J7") (pin "P1") (pinfunction "1_P1") (pintype "passive"))
      (node (ref "J8") (pin "P1") (pinfunction "1_P1") (pintype "passive"))
      (node (ref "J9") (pin "P1") (pinfunction "1_P1") (pintype "passive"))
      (node (ref "JP1") (pin "3") (pinfunction "3_3") (pintype "passive"))
      (node (ref "JP1") (pin "4") (pinfunction "4_4") (pintype "passive"))
      (node (ref "JP1") (pin "5") (pinfunction "5_5") (pintype "passive"))
      (node (ref "JP1") (pin "6") (pinfunction "6_6") (pintype "passive"))
      (node (ref "JP1") (pin "7") (pinfunction "7_7") (pintype "passive"))
      (node (ref "JP1") (pin "8") (pinfunction "8_8") (pintype "passive"))
      (node (ref "JP2") (pin "1") (pinfunction "1_1") (pintype "passive"))
      (node (ref "POT_A") (pin "P$3") (pinfunction "A_P$3") (pintype "passive"))
      (node (ref "POT_B") (pin "P$3") (pinfunction "A_P$3") (pintype "passive"))
      (node (ref "POT_C") (pin "P$3") (pinfunction "A_P$3") (pintype "passive"))
      (node (ref "Q1") (pin "2") (pinfunction "LID1_2") (pintype "power_in"))
      (node (ref "Q1") (pin "4") (pinfunction "LID2_4") (pintype "power_in"))
      (node (ref "Q2") (pin "E") (pinfunction "E_E") (pintype "passive"))
      (node (ref "Q3") (pin "E") (pinfunction "E_E") (pintype "passive"))
      (node (ref "Q4") (pin "E") (pinfunction "E_E") (pintype "passive"))
      (node (ref "R20") (pin "1") (pinfunction "1_1") (pintype "passive"))
      (node (ref "R21") (pin "1") (pinfunction "1_1") (pintype "passive"))
      (node (ref "R23") (pin "1") (pinfunction "1_1") (pintype "passive"))
      (node (ref "R45") (pin "2") (pinfunction "2_2") (pintype "passive"))
      (node (ref "R46") (pin "2") (pinfunction "2_2") (pintype "passive"))
      (node (ref "R47") (pin "2") (pinfunction "2_2") (pintype "passive"))
      (node (ref "R5") (pin "2") (pinfunction "2_2") (pintype "passive"))
      (node (ref "SLD_A") (pin "1") (pinfunction "A_1") (pintype "passive"))
      (node (ref "SLD_B") (pin "1") (pinfunction "A_1") (pintype "passive"))
      (node (ref "SLD_C") (pin "1") (pinfunction "A_1") (pintype "passive"))
      (node (ref "SW_A") (pin "1") (pinfunction "1_1") (pintype "passive"))
      (node (ref "SW_A") (pin "2") (pinfunction "2_2") (pintype "passive"))
      (node (ref "SW_B") (pin "1") (pinfunction "1_1") (pintype "passive"))
      (node (ref "SW_B") (pin "2") (pinfunction "2_2") (pintype "passive"))
      (node (ref "SW_C") (pin "1") (pinfunction "1_1") (pintype "passive"))
      (node (ref "SW_C") (pin "2") (pinfunction "2_2") (pintype "passive"))
      (node (ref "U$1") (pin "6") (pinfunction "P$6_6") (pintype "bidirectional"))
      (node (ref "U1") (pin "16") (pinfunction "VSS_2_16") (pintype "power_in"))
      (node (ref "U1") (pin "31") (pinfunction "BOOT0_31") (pintype "input"))
      (node (ref "U1") (pin "32") (pinfunction "VSS_1_32") (pintype "power_in"))
      (node (ref "U2") (pin "10") (pinfunction "+IN_10") (pintype "input"))
      (node (ref "U2") (pin "11") (pinfunction "V-_11") (pintype "power_in"))
      (node (ref "U2") (pin "12") (pinfunction "+IN_12") (pintype "input"))
      (node (ref "U2") (pin "3") (pinfunction "+IN_3") (pintype "input"))
      (node (ref "U2") (pin "5") (pinfunction "+IN_5") (pintype "input"))
      (node (ref "U3") (pin "10") (pinfunction "+IN_10") (pintype "input"))
      (node (ref "U3") (pin "12") (pinfunction "+IN_12") (pintype "input"))
      (node (ref "U3") (pin "3") (pinfunction "+IN_3") (pintype "input"))
      (node (ref "U3") (pin "5") (pinfunction "+IN_5") (pintype "input"))
    )
    (net (code "24") (name "LEDS_SCK") (class "Default")
      (node (ref "IC5") (pin "3") (pinfunction "SCLK_3") (pintype "bidirectional"))
      (node (ref "U1") (pin "26") (pinfunction "PB3_26") (pintype "bidirectional"))
    )
    (net (code "25") (name "LEDS_SIN") (class "Default")
      (node (ref "IC5") (pin "2") (pinfunction "SIN_2") (pintype "bidirectional"))
      (node (ref "U1") (pin "28") (pinfunction "PB5_28") (pintype "bidirectional"))
    )
    (net (code "26") (name "N_U") (class "Default")
      (node (ref "U2") (pin "6") (pinfunction "-IN_6") (pintype "input"))
      (node (ref "U2") (pin "7") (pinfunction "OUT_7") (pintype "output"))
    )
    (net (code "27") (name "Net-(A_OUT_LED-GRN)") (class "Default")
      (node (ref "A_OUT_LED") (pin "GREEN_C") (pinfunction "GRN_GREEN_C") (pintype "bidirectional"))
      (node (ref "IC5") (pin "13") (pinfunction "OUT8_13") (pintype "bidirectional"))
    )
    (net (code "28") (name "Net-(A_OUT_LED-RED)") (class "Default")
      (node (ref "A_OUT_LED") (pin "RED_C") (pinfunction "RED_RED_C") (pintype "bidirectional"))
      (node (ref "IC5") (pin "14") (pinfunction "OUT9_14") (pintype "bidirectional"))
    )
    (net (code "29") (name "Net-(B_OUT_LED-GRN)") (class "Default")
      (node (ref "B_OUT_LED") (pin "GREEN_C") (pinfunction "GRN_GREEN_C") (pintype "bidirectional"))
      (node (ref "IC5") (pin "16") (pinfunction "OUT11_16") (pintype "bidirectional"))
    )
    (net (code "30") (name "Net-(B_OUT_LED-RED)") (class "Default")
      (node (ref "B_OUT_LED") (pin "RED_C") (pinfunction "RED_RED_C") (pintype "bidirectional"))
      (node (ref "IC5") (pin "15") (pinfunction "OUT10_15") (pintype "bidirectional"))
    )
    (net (code "31") (name "Net-(C1-Pad1)") (class "Default")
      (node (ref "C1") (pin "1") (pinfunction "1_1") (pintype "passive"))
      (node (ref "D1") (pin "C") (pinfunction "C_C") (pintype "passive"))
      (node (ref "L1") (pin "1") (pinfunction "1_1") (pintype "passive"))
      (node (ref "L2") (pin "2") (pinfunction "2_2") (pintype "passive"))
      (node (ref "L3") (pin "2") (pinfunction "2_2") (pintype "passive"))
    )
    (net (code "32") (name "Net-(C22-Pad2)") (class "Default")
      (node (ref "C22") (pin "2") (pinfunction "2_2") (pintype "passive"))
      (node (ref "Q1") (pin "1") (pinfunction "1_1") (pintype "passive"))
      (node (ref "R6") (pin "2") (pinfunction "2_2") (pintype "passive"))
    )
    (net (code "33") (name "Net-(C_OUT_LED-GRN)") (class "Default")
      (node (ref "C_OUT_LED") (pin "GREEN_C") (pinfunction "GRN_GREEN_C") (pintype "bidirectional"))
      (node (ref "IC5") (pin "18") (pinfunction "OUT13_18") (pintype "bidirectional"))
    )
    (net (code "34") (name "Net-(C_OUT_LED-RED)") (class "Default")
      (node (ref "C_OUT_LED") (pin "RED_C") (pinfunction "RED_RED_C") (pintype "bidirectional"))
      (node (ref "IC5") (pin "17") (pinfunction "OUT12_17") (pintype "bidirectional"))
    )
    (net (code "35") (name "Net-(D2-PadA)") (class "Default")
      (node (ref "D2") (pin "A") (pinfunction "A_A") (pintype "passive"))
      (node (ref "L4") (pin "2") (pinfunction "2_2") (pintype "passive"))
    )
    (net (code "36") (name "Net-(D3-PadC)") (class "Default")
      (node (ref "D3") (pin "C") (pinfunction "C_C") (pintype "passive"))
      (node (ref "Q2") (pin "B") (pinfunction "B_B") (pintype "passive"))
      (node (ref "R18") (pin "2") (pinfunction "2_2") (pintype "passive"))
      (node (ref "R23") (pin "2") (pinfunction "2_2") (pintype "passive"))
    )
    (net (code "37") (name "Net-(D4-PadC)") (class "Default")
      (node (ref "D4") (pin "C") (pinfunction "C_C") (pintype "passive"))
      (node (ref "Q3") (pin "B") (pinfunction "B_B") (pintype "passive"))
      (node (ref "R19") (pin "2") (pinfunction "2_2") (pintype "passive"))
      (node (ref "R20") (pin "2") (pinfunction "2_2") (pintype "passive"))
    )
    (net (code "38") (name "Net-(D5-PadC)") (class "Default")
      (node (ref "D5") (pin "C") (pinfunction "C_C") (pintype "passive"))
      (node (ref "Q4") (pin "B") (pinfunction "B_B") (pintype "passive"))
      (node (ref "R21") (pin "2") (pinfunction "2_2") (pintype "passive"))
      (node (ref "R22") (pin "2") (pinfunction "2_2") (pintype "passive"))
    )
    (net (code "39") (name "Net-(IC1-VI)") (class "Default")
      (node (ref "C5") (pin "1") (pinfunction "1_1") (pintype "passive"))
      (node (ref "IC1") (pin "1") (pinfunction "VI_1") (pintype "input"))
      (node (ref "L1") (pin "2") (pinfunction "2_2") (pintype "passive"))
    )
    (net (code "40") (name "Net-(IC2-VI)") (class "Default")
      (node (ref "C3") (pin "1") (pinfunction "1_1") (pintype "passive"))
      (node (ref "IC2") (pin "3") (pinfunction "VI_3") (pintype "input"))
      (node (ref "L2") (pin "1") (pinfunction "1_1") (pintype "passive"))
    )
    (net (code "41") (name "Net-(IC4A-X0)") (class "Default")
      (node (ref "IC4") (pin "13") (pinfunction "X0_13") (pintype "bidirectional"))
      (node (ref "POT_C") (pin "P$2") (pinfunction "S_P$2") (pintype "passive"))
    )
    (net (code "42") (name "Net-(IC4A-X1)") (class "Default")
      (node (ref "IC4") (pin "14") (pinfunction "X1_14") (pintype "bidirectional"))
      (node (ref "SLD_C") (pin "2") (pinfunction "S_2") (pintype "passive"))
    )
    (net (code "43") (name "Net-(IC4A-X2)") (class "Default")
      (node (ref "IC4") (pin "15") (pinfunction "X2_15") (pintype "bidirectional"))
      (node (ref "SLD_B") (pin "2") (pinfunction "S_2") (pintype "passive"))
    )
    (net (code "44") (name "Net-(IC4A-X3)") (class "Default")
      (node (ref "IC4") (pin "12") (pinfunction "X3_12") (pintype "bidirectional"))
      (node (ref "POT_A") (pin "P$2") (pinfunction "S_P$2") (pintype "passive"))
    )
    (net (code "45") (name "Net-(IC4A-X4)") (class "Default")
      (node (ref "IC4") (pin "1") (pinfunction "X4_1") (pintype "bidirectional"))
      (node (ref "SLD_A") (pin "2") (pinfunction "S_2") (pintype "passive"))
    )
    (net (code "46") (name "Net-(IC4A-X6)") (class "Default")
      (node (ref "IC4") (pin "2") (pinfunction "X6_2") (pintype "bidirectional"))
      (node (ref "POT_B") (pin "P$2") (pinfunction "S_P$2") (pintype "passive"))
    )
    (net (code "47") (name "Net-(IC5-IREF)") (class "Default")
      (node (ref "IC5") (pin "23") (pinfunction "IREF_23") (pintype "bidirectional"))
      (node (ref "R5") (pin "1") (pinfunction "1_1") (pintype "passive"))
    )
    (net (code "48") (name "Net-(IC5-OUT1)") (class "Default")
      (node (ref "IC5") (pin "6") (pinfunction "OUT1_6") (pintype "bidirectional"))
      (node (ref "R15") (pin "2") (pinfunction "2_2") (pintype "passive"))
    )
    (net (code "49") (name "Net-(IC5-OUT2)") (class "Default")
      (node (ref "IC5") (pin "7") (pinfunction "OUT2_7") (pintype "bidirectional"))
      (node (ref "MODE_C") (pin "RED_C") (pinfunction "RED_RED_C") (pintype "bidirectional"))
    )
    (net (code "50") (name "Net-(IC5-OUT3)") (class "Default")
      (node (ref "IC5") (pin "8") (pinfunction "OUT3_8") (pintype "bidirectional"))
      (node (ref "MODE_C") (pin "GREEN_C") (pinfunction "GRN_GREEN_C") (pintype "bidirectional"))
    )
    (net (code "51") (name "Net-(IC5-OUT4)") (class "Default")
      (node (ref "IC5") (pin "9") (pinfunction "OUT4_9") (pintype "bidirectional"))
      (node (ref "MODE_A") (pin "GREEN_C") (pinfunction "GRN_GREEN_C") (pintype "bidirectional"))
    )
    (net (code "52") (name "Net-(IC5-OUT5)") (class "Default")
      (node (ref "IC5") (pin "10") (pinfunction "OUT5_10") (pintype "bidirectional"))
      (node (ref "MODE_A") (pin "RED_C") (pinfunction "RED_RED_C") (pintype "bidirectional"))
    )
    (net (code "53") (name "Net-(IC5-OUT6)") (class "Default")
      (node (ref "IC5") (pin "11") (pinfunction "OUT6_11") (pintype "bidirectional"))
      (node (ref "MODE_B") (pin "GREEN_C") (pinfunction "GRN_GREEN_C") (pintype "bidirectional"))
    )
    (net (code "54") (name "Net-(IC5-OUT7)") (class "Default")
      (node (ref "IC5") (pin "12") (pinfunction "OUT7_12") (pintype "bidirectional"))
      (node (ref "MODE_B") (pin "RED_C") (pinfunction "RED_RED_C") (pintype "bidirectional"))
    )
    (net (code "55") (name "Net-(IC5-OUT14)") (class "Default")
      (node (ref "IC5") (pin "19") (pinfunction "OUT14_19") (pintype "bidirectional"))
      (node (ref "R16") (pin "2") (pinfunction "2_2") (pintype "passive"))
    )
    (net (code "56") (name "Net-(IC5-OUT15)") (class "Default")
      (node (ref "IC5") (pin "20") (pinfunction "OUT15_20") (pintype "bidirectional"))
      (node (ref "R17") (pin "2") (pinfunction "2_2") (pintype "passive"))
    )
    (net (code "57") (name "Net-(IC5-VCC)") (class "Default")
      (node (ref "C14") (pin "1") (pinfunction "1_1") (pintype "passive"))
      (node (ref "C15") (pin "1") (pinfunction "1_1") (pintype "passive"))
      (node (ref "IC5") (pin "24") (pinfunction "VCC_24") (pintype "bidirectional"))
      (node (ref "L5") (pin "1") (pinfunction "1_1") (pintype "passive"))
    )
    (net (code "58") (name "Net-(IC6A-+IN)") (class "Default")
      (node (ref "IC6") (pin "3") (pinfunction "+IN_3") (pintype "input"))
      (node (ref "R44") (pin "2") (pinfunction "2_2") (pintype "passive"))
      (node (ref "R47") (pin "1") (pinfunction "1_1") (pintype "passive"))
    )
    (net (code "59") (name "Net-(IC6A--IN)") (class "Default")
      (node (ref "IC6") (pin "2") (pinfunction "-IN_2") (pintype "input"))
      (node (ref "R13") (pin "1") (pinfunction "1_1") (pintype "passive"))
    )
    (net (code "60") (name "Net-(IC6A-OUT)") (class "Default")
      (node (ref "IC6") (pin "1") (pinfunction "OUT_1") (pintype "output"))
      (node (ref "R39") (pin "2") (pinfunction "2_2") (pintype "passive"))
      (node (ref "R44") (pin "1") (pinfunction "1_1") (pintype "passive"))
    )
    (net (code "61") (name "Net-(IC6B-+IN)") (class "Default")
      (node (ref "IC6") (pin "5") (pinfunction "+IN_5") (pintype "input"))
      (node (ref "R41") (pin "2") (pinfunction "2_2") (pintype "passive"))
      (node (ref "R46") (pin "1") (pinfunction "1_1") (pintype "passive"))
    )
    (net (code "62") (name "Net-(IC6B--IN)") (class "Default")
      (node (ref "IC6") (pin "6") (pinfunction "-IN_6") (pintype "input"))
      (node (ref "R12") (pin "1") (pinfunction "1_1") (pintype "passive"))
    )
    (net (code "63") (name "Net-(IC6B-OUT)") (class "Default")
      (node (ref "IC6") (pin "7") (pinfunction "OUT_7") (pintype "output"))
      (node (ref "R38") (pin "2") (pinfunction "2_2") (pintype "passive"))
      (node (ref "R41") (pin "1") (pinfunction "1_1") (pintype "passive"))
    )
    (net (code "64") (name "Net-(IC6C-+IN)") (class "Default")
      (node (ref "IC6") (pin "10") (pinfunction "+IN_10") (pintype "input"))
      (node (ref "R36") (pin "2") (pinfunction "2_2") (pintype "passive"))
      (node (ref "R45") (pin "1") (pinfunction "1_1") (pintype "passive"))
    )
    (net (code "65") (name "Net-(IC6C--IN)") (class "Default")
      (node (ref "IC6") (pin "9") (pinfunction "-IN_9") (pintype "input"))
      (node (ref "R11") (pin "1") (pinfunction "1_1") (pintype "passive"))
    )
    (net (code "66") (name "Net-(IC6C-OUT)") (class "Default")
      (node (ref "IC6") (pin "8") (pinfunction "OUT_8") (pintype "output"))
      (node (ref "R36") (pin "1") (pinfunction "1_1") (pintype "passive"))
      (node (ref "R37") (pin "2") (pinfunction "2_2") (pintype "passive"))
    )
    (net (code "67") (name "Net-(IC6D--IN)") (class "Default")
      (node (ref "IC6") (pin "13") (pinfunction "-IN_13") (pintype "input"))
      (node (ref "IC6") (pin "14") (pinfunction "OUT_14") (pintype "output"))
    )
    (net (code "68") (name "Net-(J4-3)") (class "Default")
      (node (ref "J4") (pin "P3") (pinfunction "3_P3") (pintype "passive"))
      (node (ref "R24") (pin "2") (pinfunction "2_2") (pintype "passive"))
    )
    (net (code "69") (name "Net-(J6-3)") (class "Default")
      (node (ref "J6") (pin "P3") (pinfunction "3_P3") (pintype "passive"))
      (node (ref "R26") (pin "2") (pinfunction "2_2") (pintype "passive"))
    )
    (net (code "70") (name "Net-(J7-3)") (class "Default")
      (node (ref "J7") (pin "P3") (pinfunction "3_P3") (pintype "passive"))
      (node (ref "R37") (pin "1") (pinfunction "1_1") (pintype "passive"))
    )
    (net (code "71") (name "Net-(J8-3)") (class "Default")
      (node (ref "J8") (pin "P3") (pinfunction "3_P3") (pintype "passive"))
      (node (ref "R38") (pin "1") (pinfunction "1_1") (pintype "passive"))
    )
    (net (code "72") (name "Net-(J9-3)") (class "Default")
      (node (ref "J9") (pin "P3") (pinfunction "3_P3") (pintype "passive"))
      (node (ref "R39") (pin "1") (pinfunction "1_1") (pintype "passive"))
    )
    (net (code "73") (name "Net-(J10-3)") (class "Default")
      (node (ref "J10") (pin "P3") (pinfunction "3_P3") (pintype "passive"))
      (node (ref "R35") (pin "1") (pinfunction "1_1") (pintype "passive"))
      (node (ref "R40") (pin "1") (pinfunction "1_1") (pintype "passive"))
    )
    (net (code "74") (name "Net-(J11-3)") (class "Default")
      (node (ref "J11") (pin "P3") (pinfunction "3_P3") (pintype "passive"))
      (node (ref "R29") (pin "1") (pinfunction "1_1") (pintype "passive"))
      (node (ref "R42") (pin "1") (pinfunction "1_1") (pintype "passive"))
    )
    (net (code "75") (name "Net-(J12-3)") (class "Default")
      (node (ref "J12") (pin "P3") (pinfunction "3_P3") (pintype "passive"))
      (node (ref "R32") (pin "1") (pinfunction "1_1") (pintype "passive"))
      (node (ref "R43") (pin "1") (pinfunction "1_1") (pintype "passive"))
    )
    (net (code "76") (name "Net-(Q1B-2)") (class "Default")
      (node (ref "C21") (pin "2") (pinfunction "2_2") (pintype "passive"))
      (node (ref "Q1") (pin "3") (pinfunction "2_3") (pintype "passive"))
      (node (ref "R9") (pin "2") (pinfunction "2_2") (pintype "passive"))
    )
    (net (code "77") (name "Net-(SLD_AA-C)") (class "Default")
      (node (ref "R16") (pin "1") (pinfunction "1_1") (pintype "passive"))
      (node (ref "SLD_A") (pin "E") (pinfunction "C_E") (pintype "passive"))
    )
    (net (code "78") (name "Net-(SLD_BA-C)") (class "Default")
      (node (ref "R17") (pin "1") (pinfunction "1_1") (pintype "passive"))
      (node (ref "SLD_B") (pin "E") (pinfunction "C_E") (pintype "passive"))
    )
    (net (code "79") (name "Net-(SLD_CA-C)") (class "Default")
      (node (ref "R15") (pin "1") (pinfunction "1_1") (pintype "passive"))
      (node (ref "SLD_C") (pin "E") (pinfunction "C_E") (pintype "passive"))
    )
    (net (code "80") (name "Net-(U1-PF0{slash}OSC_IN)") (class "Default")
      (node (ref "R9") (pin "1") (pinfunction "1_1") (pintype "passive"))
      (node (ref "U1") (pin "2") (pinfunction "PF0/OSC_IN_2") (pintype "bidirectional"))
    )
    (net (code "81") (name "Net-(U1-PF1{slash}OSC_OUT)") (class "Default")
      (node (ref "R6") (pin "1") (pinfunction "1_1") (pintype "passive"))
      (node (ref "U1") (pin "3") (pinfunction "PF1/OSC_OUT_3") (pintype "bidirectional"))
    )
    (net (code "82") (name "Net-(U2A--IN)") (class "Default")
      (node (ref "C30") (pin "1") (pinfunction "1_1") (pintype "passive"))
      (node (ref "R14") (pin "2") (pinfunction "2_2") (pintype "passive"))
      (node (ref "R2") (pin "1") (pinfunction "1_1") (pintype "passive"))
      (node (ref "R26") (pin "1") (pinfunction "1_1") (pintype "passive"))
      (node (ref "U2") (pin "2") (pinfunction "-IN_2") (pintype "input"))
    )
    (net (code "83") (name "Net-(U2C--IN)") (class "Default")
      (node (ref "C23") (pin "1") (pinfunction "1_1") (pintype "passive"))
      (node (ref "R25") (pin "1") (pinfunction "1_1") (pintype "passive"))
      (node (ref "R3") (pin "1") (pinfunction "1_1") (pintype "passive"))
      (node (ref "R7") (pin "2") (pinfunction "2_2") (pintype "passive"))
      (node (ref "U2") (pin "9") (pinfunction "-IN_9") (pintype "input"))
    )
    (net (code "84") (name "Net-(U2D--IN)") (class "Default")
      (node (ref "C24") (pin "1") (pinfunction "1_1") (pintype "passive"))
      (node (ref "R24") (pin "1") (pinfunction "1_1") (pintype "passive"))
      (node (ref "R4") (pin "1") (pinfunction "1_1") (pintype "passive"))
      (node (ref "R8") (pin "2") (pinfunction "2_2") (pintype "passive"))
      (node (ref "U2") (pin "13") (pinfunction "-IN_13") (pintype "input"))
    )
    (net (code "85") (name "Net-(U3A--IN)") (class "Default")
      (node (ref "C33") (pin "1") (pinfunction "1_1") (pintype "passive"))
      (node (ref "R30") (pin "1") (pinfunction "1_1") (pintype "passive"))
      (node (ref "R31") (pin "1") (pinfunction "1_1") (pintype "passive"))
      (node (ref "R32") (pin "2") (pinfunction "2_2") (pintype "passive"))
      (node (ref "U3") (pin "2") (pinfunction "-IN_2") (pintype "input"))
    )
    (net (code "86") (name "Net-(U3A-OUT)") (class "Default")
      (node (ref "C33") (pin "2") (pinfunction "2_2") (pintype "passive"))
      (node (ref "R43") (pin "2") (pinfunction "2_2") (pintype "passive"))
      (node (ref "U3") (pin "1") (pinfunction "OUT_1") (pintype "output"))
    )
    (net (code "87") (name "Net-(U3B--IN)") (class "Default")
      (node (ref "C32") (pin "1") (pinfunction "1_1") (pintype "passive"))
      (node (ref "R27") (pin "1") (pinfunction "1_1") (pintype "passive"))
      (node (ref "R28") (pin "1") (pinfunction "1_1") (pintype "passive"))
      (node (ref "R29") (pin "2") (pinfunction "2_2") (pintype "passive"))
      (node (ref "U3") (pin "6") (pinfunction "-IN_6") (pintype "input"))
    )
    (net (code "88") (name "Net-(U3B-OUT)") (class "Default")
      (node (ref "C32") (pin "2") (pinfunction "2_2") (pintype "passive"))
      (node (ref "R42") (pin "2") (pinfunction "2_2") (pintype "passive"))
      (node (ref "U3") (pin "7") (pinfunction "OUT_7") (pintype "output"))
    )
    (net (code "89") (name "Net-(U3C--IN)") (class "Default")
      (node (ref "C34") (pin "1") (pinfunction "1_1") (pintype "passive"))
      (node (ref "R33") (pin "1") (pinfunction "1_1") (pintype "passive"))
      (node (ref "R34") (pin "1") (pinfunction "1_1") (pintype "passive"))
      (node (ref "R35") (pin "2") (pinfunction "2_2") (pintype "passive"))
      (node (ref "U3") (pin "9") (pinfunction "-IN_9") (pintype "input"))
    )
    (net (code "90") (name "Net-(U3C-OUT)") (class "Default")
      (node (ref "C34") (pin "2") (pinfunction "2_2") (pintype "passive"))
      (node (ref "R40") (pin "2") (pinfunction "2_2") (pintype "passive"))
      (node (ref "U3") (pin "8") (pinfunction "OUT_8") (pintype "output"))
    )
    (net (code "91") (name "Net-(U3D--IN)") (class "Default")
      (node (ref "U3") (pin "13") (pinfunction "-IN_13") (pintype "input"))
      (node (ref "U3") (pin "14") (pinfunction "OUT_14") (pintype "output"))
    )
    (net (code "92") (name "POTS_ADDR_A") (class "Default")
      (node (ref "IC4") (pin "11") (pinfunction "A_11") (pintype "input"))
      (node (ref "U1") (pin "13") (pinfunction "PA7_13") (pintype "bidirectional"))
    )
    (net (code "93") (name "POTS_ADDR_B") (class "Default")
      (node (ref "IC4") (pin "10") (pinfunction "B_10") (pintype "input"))
      (node (ref "U1") (pin "18") (pinfunction "PA8_18") (pintype "bidirectional"))
    )
    (net (code "94") (name "POTS_ADDR_C") (class "Default")
      (node (ref "IC4") (pin "9") (pinfunction "C_9") (pintype "input"))
      (node (ref "U1") (pin "19") (pinfunction "PA9_19") (pintype "bidirectional"))
    )
    (net (code "95") (name "RESET") (class "Default")
      (node (ref "C28") (pin "1") (pinfunction "1_1") (pintype "passive"))
      (node (ref "JP2") (pin "4") (pinfunction "4_4") (pintype "passive"))
      (node (ref "R10") (pin "2") (pinfunction "2_2") (pintype "passive"))
      (node (ref "U1") (pin "4") (pinfunction "NRST_4") (pintype "bidirectional"))
    )
    (net (code "96") (name "SWCLK") (class "Default")
      (node (ref "JP2") (pin "3") (pinfunction "3_3") (pintype "passive"))
      (node (ref "U1") (pin "24") (pinfunction "PA14_24") (pintype "bidirectional"))
    )
    (net (code "97") (name "SWDIO") (class "Default")
      (node (ref "JP2") (pin "2") (pinfunction "2_2") (pintype "passive"))
      (node (ref "U1") (pin "23") (pinfunction "PA13_23") (pintype "bidirectional"))
    )
    (net (code "98") (name "SW_MODE_A") (class "Default")
      (node (ref "SW_A") (pin "3") (pinfunction "3_3") (pintype "passive"))
      (node (ref "SW_A") (pin "4") (pinfunction "4_4") (pintype "passive"))
      (node (ref "U1") (pin "27") (pinfunction "PB4_27") (pintype "bidirectional"))
    )
    (net (code "99") (name "SW_MODE_B") (class "Default")
      (node (ref "SW_B") (pin "3") (pinfunction "3_3") (pintype "passive"))
      (node (ref "SW_B") (pin "4") (pinfunction "4_4") (pintype "passive"))
      (node (ref "U1") (pin "29") (pinfunction "PB6_29") (pintype "bidirectional"))
    )
    (net (code "100") (name "SW_MODE_C") (class "Default")
      (node (ref "SW_C") (pin "3") (pinfunction "3_3") (pintype "passive"))
      (node (ref "SW_C") (pin "4") (pinfunction "4_4") (pintype "passive"))
      (node (ref "U1") (pin "30") (pinfunction "PB7_30") (pintype "bidirectional"))
    )
    (net (code "101") (name "VCC") (class "Default")
      (node (ref "C2") (pin "1") (pinfunction "1_1") (pintype "passive"))
      (node (ref "C31") (pin "1") (pinfunction "1_1") (pintype "passive"))
      (node (ref "C35") (pin "1") (pinfunction "1_1") (pintype "passive"))
      (node (ref "C4") (pin "1") (pinfunction "1_1") (pintype "passive"))
      (node (ref "IC6") (pin "4") (pinfunction "V+_4") (pintype "power_in"))
      (node (ref "L3") (pin "1") (pinfunction "1_1") (pintype "passive"))
      (node (ref "U$1") (pin "1") (pinfunction "P$1_1") (pintype "bidirectional"))
      (node (ref "U3") (pin "4") (pinfunction "V+_4") (pintype "power_in"))
    )
    (net (code "102") (name "VEE") (class "Default")
      (node (ref "C10") (pin "2") (pinfunction "2_2") (pintype "passive"))
      (node (ref "C25") (pin "2") (pinfunction "2_2") (pintype "passive"))
      (node (ref "C9") (pin "2") (pinfunction "2_2") (pintype "passive"))
      (node (ref "L4") (pin "1") (pinfunction "1_1") (pintype "passive"))
      (node (ref "R1") (pin "1") (pinfunction "1_1") (pintype "passive"))
      (node (ref "U$1") (pin "2") (pinfunction "P$2_2") (pintype "bidirectional"))
      (node (ref "U3") (pin "11") (pinfunction "V-_11") (pintype "power_in"))
    )
    (net (code "103") (name "unconnected-(IC4A-X5-Pad5)") (class "Default")
      (node (ref "IC4") (pin "5") (pinfunction "X5_5") (pintype "bidirectional"))
    )
    (net (code "104") (name "unconnected-(IC4A-X7-Pad4)") (class "Default")
      (node (ref "IC4") (pin "4") (pinfunction "X7_4") (pintype "bidirectional"))
    )
    (net (code "105") (name "unconnected-(IC5-LAT-Pad4)") (class "Default")
      (node (ref "IC5") (pin "4") (pinfunction "LAT_4") (pintype "bidirectional"))
    )
    (net (code "106") (name "unconnected-(IC5-OUT0-Pad5)") (class "Default")
      (node (ref "IC5") (pin "5") (pinfunction "OUT0_5") (pintype "bidirectional"))
    )
    (net (code "107") (name "unconnected-(IC5-SOUT-Pad22)") (class "Default")
      (node (ref "IC5") (pin "22") (pinfunction "SOUT_22") (pintype "bidirectional"))
    )
    (net (code "108") (name "unconnected-(J7-2-PadP2)") (class "Default")
      (node (ref "J7") (pin "P2") (pinfunction "2_P2") (pintype "passive"))
    )
    (net (code "109") (name "unconnected-(J8-2-PadP2)") (class "Default")
      (node (ref "J8") (pin "P2") (pinfunction "2_P2") (pintype "passive"))
    )
    (net (code "110") (name "unconnected-(J9-2-PadP2)") (class "Default")
      (node (ref "J9") (pin "P2") (pinfunction "2_P2") (pintype "passive"))
    )
    (net (code "111") (name "unconnected-(J10-2-PadP2)") (class "Default")
      (node (ref "J10") (pin "P2") (pinfunction "2_P2") (pintype "passive"))
    )
    (net (code "112") (name "unconnected-(J11-2-PadP2)") (class "Default")
      (node (ref "J11") (pin "P2") (pinfunction "2_P2") (pintype "passive"))
    )
    (net (code "113") (name "unconnected-(J12-2-PadP2)") (class "Default")
      (node (ref "J12") (pin "P2") (pinfunction "2_P2") (pintype "passive"))
    )
  )
)
